# MINI_SAM_2017-01-015.net
KiCad netlist of a schematic drawn in EAGLE
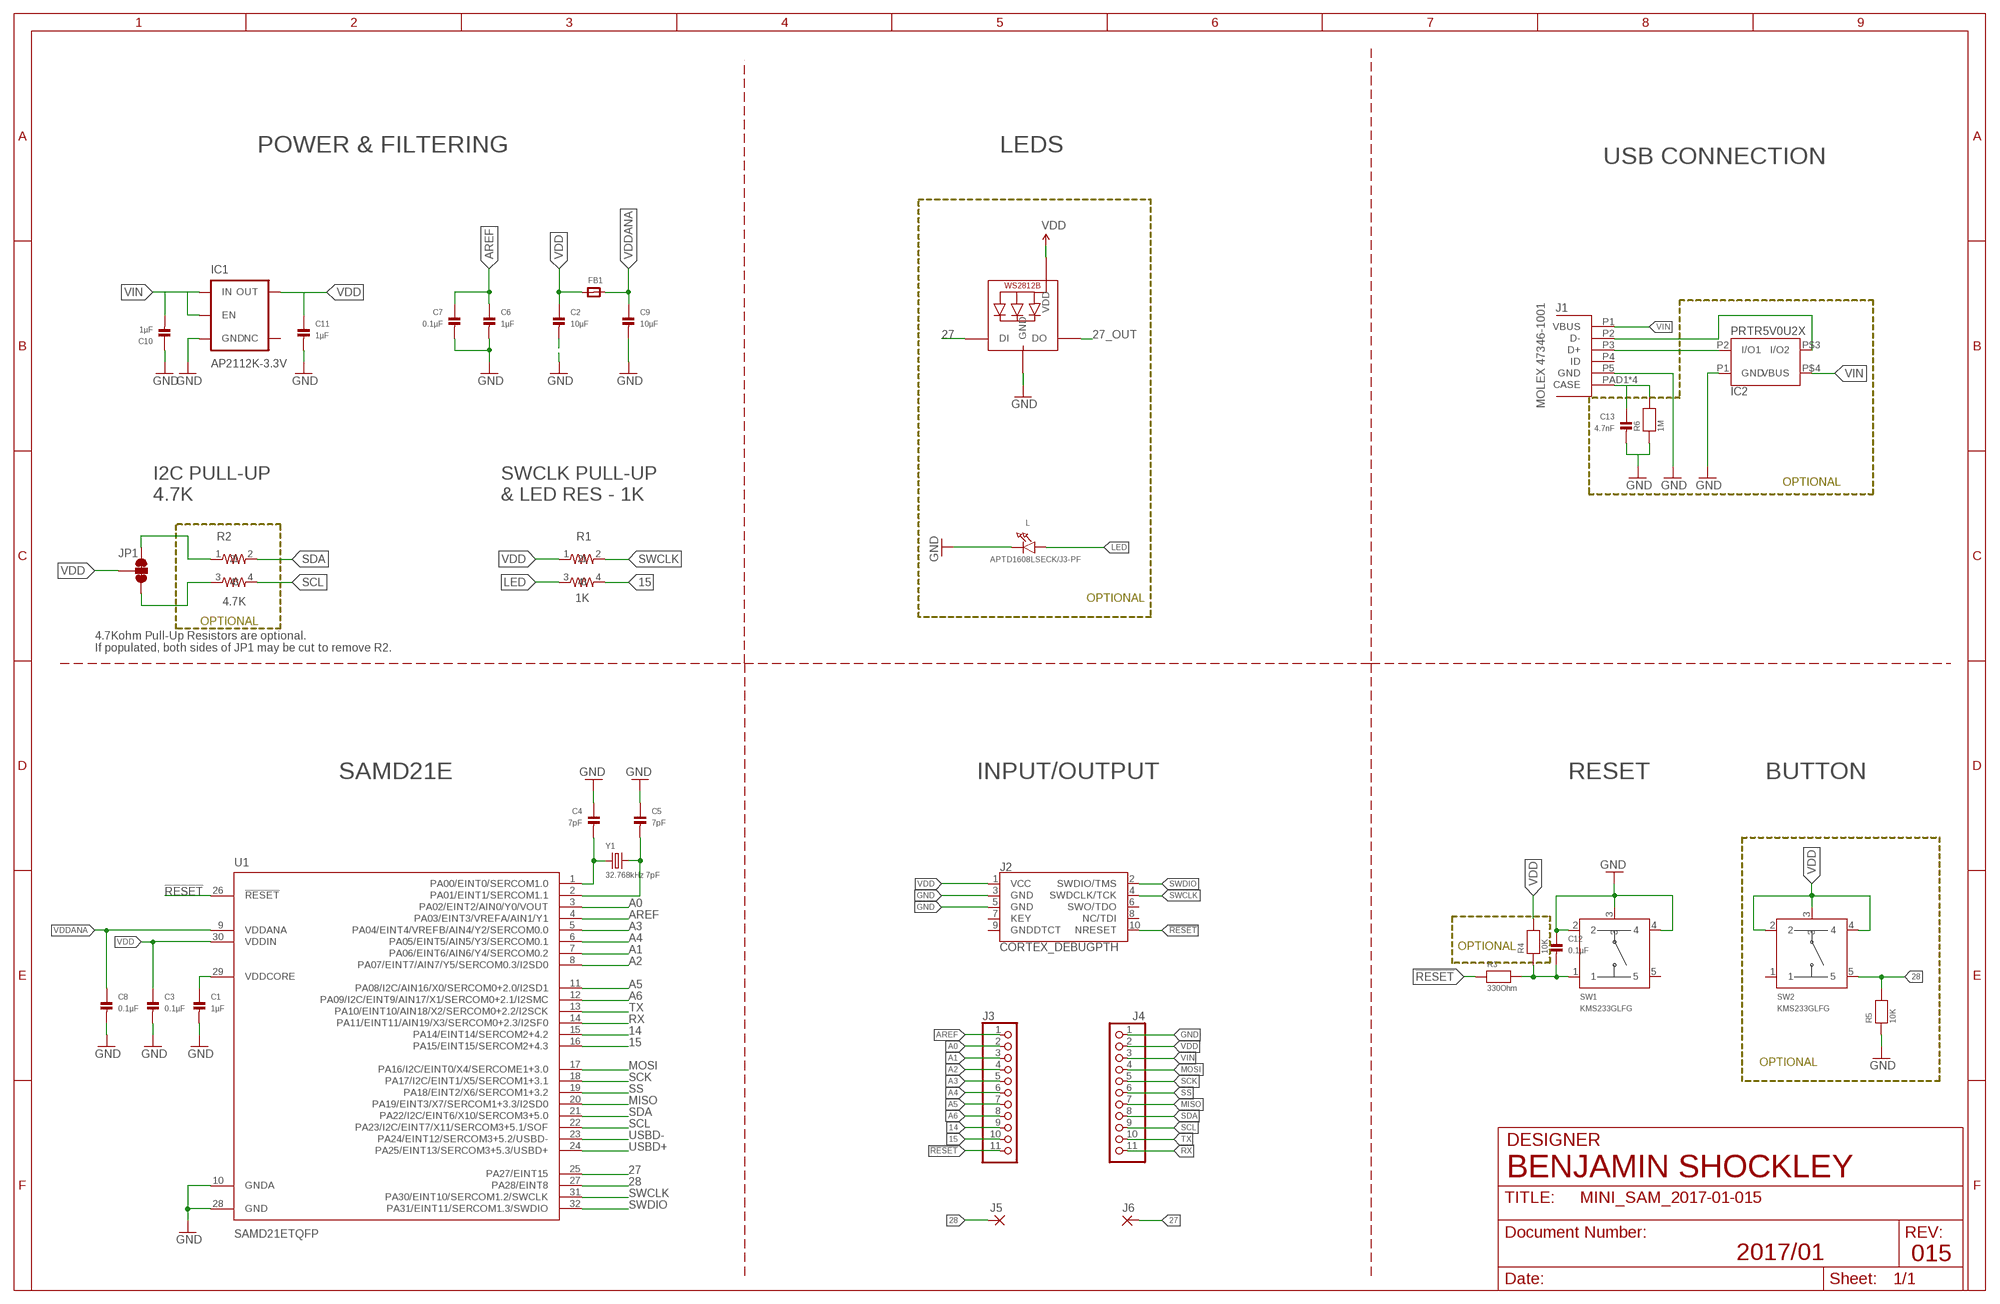
[diagram p0: schematic, sheet 1]

(export (version "E")
  (design (tool "Eeschema 10.0.6"))
  (components
    (comp (ref "C1")
      (value "1µF")
      (footprint "eagle-import:_0805MP")
      (libsource (lib "eagle-import") (part "CAP_CERAMIC_0805MP"))
    )
    (comp (ref "C2")
      (value "10µF")
      (footprint "eagle-import:_0805MP")
      (libsource (lib "eagle-import") (part "CAP_CERAMIC_0805MP"))
    )
    (comp (ref "C3")
      (value "0.1µF")
      (footprint "eagle-import:_0805MP")
      (libsource (lib "eagle-import") (part "CAP_CERAMIC_0805MP"))
    )
    (comp (ref "C4")
      (value "7pF")
      (footprint "eagle-import:_0805MP")
      (libsource (lib "eagle-import") (part "CAP_CERAMIC_0805MP"))
    )
    (comp (ref "C5")
      (value "7pF")
      (footprint "eagle-import:_0805MP")
      (libsource (lib "eagle-import") (part "CAP_CERAMIC_0805MP"))
    )
    (comp (ref "C6")
      (value "1µF")
      (footprint "eagle-import:_0805MP")
      (libsource (lib "eagle-import") (part "CAP_CERAMIC_0805MP"))
    )
    (comp (ref "C7")
      (value "0.1µF")
      (footprint "eagle-import:_0805MP")
      (libsource (lib "eagle-import") (part "CAP_CERAMIC_0805MP"))
    )
    (comp (ref "C8")
      (value "0.1µF")
      (footprint "eagle-import:_0805MP")
      (libsource (lib "eagle-import") (part "CAP_CERAMIC_0805MP"))
    )
    (comp (ref "C9")
      (value "10µF")
      (footprint "eagle-import:_0805MP")
      (libsource (lib "eagle-import") (part "CAP_CERAMIC_0805MP"))
    )
    (comp (ref "C10")
      (value "1µF")
      (footprint "eagle-import:_0805MP")
      (libsource (lib "eagle-import") (part "CAP_CERAMIC_0805MP"))
    )
    (comp (ref "C11")
      (value "1µF")
      (footprint "eagle-import:_0805MP")
      (libsource (lib "eagle-import") (part "CAP_CERAMIC_0805MP"))
    )
    (comp (ref "C12")
      (value "0.1µF")
      (footprint "eagle-import:_0805MP")
      (libsource (lib "eagle-import") (part "CAP_CERAMIC_0805MP"))
    )
    (comp (ref "C13")
      (value "4.7nF")
      (footprint "eagle-import:_0805MP")
      (libsource (lib "eagle-import") (part "CAP_CERAMIC_0805MP"))
    )
    (comp (ref "FB1")
      (value "FERRITE_0805MP")
      (footprint "eagle-import:_0805MP")
      (libsource (lib "eagle-import") (part "FERRITE_0805MP"))
    )
    (comp (ref "IC1")
      (value "AP2112K-3.3V")
      (footprint "eagle-import:SOT23-5")
      (libsource (lib "eagle-import") (part "V_REG_AP2112K-3.3V"))
    )
    (comp (ref "IC2")
      (value "PRTR5V0U2X")
      (footprint "eagle-import:SOT143B_REFLOW")
      (libsource (lib "eagle-import") (part "PRTR5V0U2X"))
    )
    (comp (ref "J1")
      (value "MOLEX_47346-100147346")
      (footprint "eagle-import:MOLEX_47346-1001")
      (libsource (lib "eagle-import") (part "MOLEX_47346-100147346"))
    )
    (comp (ref "J2")
      (value "CORTEX_DEBUGPTH")
      (footprint "eagle-import:2X5-PTH-1.27MM")
      (libsource (lib "eagle-import") (part "CORTEX_DEBUGPTH"))
    )
    (comp (ref "J3")
      (value "PINHD-1X111X11_SMT")
      (footprint "eagle-import:1X11_SMT")
      (libsource (lib "eagle-import") (part "PINHD-1X111X11_SMT"))
    )
    (comp (ref "J4")
      (value "PINHD-1X111X11_SMT")
      (footprint "eagle-import:1X11_SMT")
      (libsource (lib "eagle-import") (part "PINHD-1X111X11_SMT"))
    )
    (comp (ref "J5")
      (value "FR11_PAD2MMX1MM")
      (footprint "eagle-import:SMD2MMX1MM")
      (libsource (lib "eagle-import") (part "FR11_PAD2MMX1MM"))
    )
    (comp (ref "J6")
      (value "FR11_PAD2MMX1MM")
      (footprint "eagle-import:SMD2MMX1MM")
      (libsource (lib "eagle-import") (part "FR11_PAD2MMX1MM"))
    )
    (comp (ref "JP1")
      (value "JUMPER-SMT_3_2-NC_TRACE_NO-SILK")
      (footprint "eagle-import:SMT-JUMPER_3_2-NC_TRACE_NO-SILK")
      (libsource (lib "eagle-import") (part "JUMPER-SMT_3_2-NC_TRACE_NO-SILK"))
    )
    (comp (ref "L")
      (value "APTD1608LSECK/J3-PF")
      (footprint "eagle-import:CHIPLED_0603_NOOUTLINE")
      (libsource (lib "eagle-import") (part "LED0603_NOOUTLINE"))
    )
    (comp (ref "R1")
      (value "1K")
      (footprint "eagle-import:RESISTOR_ARRAY_0606")
      (libsource (lib "eagle-import") (part "RESISTOR_ARRAY_2"))
    )
    (comp (ref "R2")
      (value "4.7K")
      (footprint "eagle-import:RESISTOR_ARRAY_0606")
      (libsource (lib "eagle-import") (part "RESISTOR_ARRAY_2"))
    )
    (comp (ref "R3")
      (value "330Ohm")
      (footprint "eagle-import:_0805MP")
      (libsource (lib "eagle-import") (part "RESISTOR_0805MP"))
    )
    (comp (ref "R4")
      (value "10K")
      (footprint "eagle-import:_0805MP")
      (libsource (lib "eagle-import") (part "RESISTOR_0805MP"))
    )
    (comp (ref "R5")
      (value "10K")
      (footprint "eagle-import:_0805MP")
      (libsource (lib "eagle-import") (part "RESISTOR_0805MP"))
    )
    (comp (ref "R6")
      (value "1M")
      (footprint "eagle-import:_0805MP")
      (libsource (lib "eagle-import") (part "RESISTOR_0805MP"))
    )
    (comp (ref "STATUS")
      (value "WS2812B3535")
      (footprint "eagle-import:LED3535")
      (libsource (lib "eagle-import") (part "WS2812B3535"))
    )
    (comp (ref "SW1")
      (value "KMS233GLFG")
      (footprint "eagle-import:KMS_SWITCH")
      (libsource (lib "eagle-import") (part "KMS_SWITCHKMS"))
    )
    (comp (ref "SW2")
      (value "KMS233GLFG")
      (footprint "eagle-import:KMS_SWITCH")
      (libsource (lib "eagle-import") (part "KMS_SWITCHKMS"))
    )
    (comp (ref "U1")
      (value "SAMD21ETQFP")
      (footprint "eagle-import:TQFP32-08")
      (libsource (lib "eagle-import") (part "SAMD21ETQFP"))
    )
    (comp (ref "Y1")
      (value "32.768kHz 7pF")
      (footprint "eagle-import:_0805MP")
      (libsource (lib "eagle-import") (part "CRYSTAL0805PACKAGE"))
    )
  )
  (nets
    (net (code "1") (name "/27_OUT") (class "Default")
      (node (ref "STATUS") (pin "3") (pinfunction "DO_3") (pintype "output"))
    )
    (net (code "2") (name "/USBD+") (class "Default")
      (node (ref "IC2") (pin "P2") (pinfunction "I/O1_P2") (pintype "bidirectional"))
      (node (ref "J1") (pin "P3") (pinfunction "D+_P3") (pintype "bidirectional"))
      (node (ref "U1") (pin "24") (pinfunction "PA25/EINT13/SERCOM3+5.3/USBD+_24") (pintype "bidirectional"))
    )
    (net (code "3") (name "/USBD-") (class "Default")
      (node (ref "IC2") (pin "P$3") (pinfunction "I/O2_P$3") (pintype "bidirectional"))
      (node (ref "J1") (pin "P2") (pinfunction "D-_P2") (pintype "bidirectional"))
      (node (ref "U1") (pin "23") (pinfunction "PA24/EINT12/SERCOM3+5.2/USBD-_23") (pintype "bidirectional"))
    )
    (net (code "4") (name "/~{RESET}") (class "Default")
      (node (ref "J2") (pin "10") (pinfunction "NRESET_10") (pintype "bidirectional"))
      (node (ref "J3") (pin "11") (pinfunction "11_11") (pintype "passive"))
      (node (ref "R3") (pin "1") (pinfunction "1_1") (pintype "passive"))
      (node (ref "U1") (pin "26") (pinfunction "~{RESET}_26") (pintype "bidirectional"))
    )
    (net (code "5") (name "14") (class "Default")
      (node (ref "J3") (pin "9") (pinfunction "9_9") (pintype "passive"))
      (node (ref "U1") (pin "15") (pinfunction "PA14/EINT14/SERCOM2+4.2_15") (pintype "bidirectional"))
    )
    (net (code "6") (name "15") (class "Default")
      (node (ref "J3") (pin "10") (pinfunction "10_10") (pintype "passive"))
      (node (ref "R1") (pin "4") (pinfunction "4_4") (pintype "passive"))
      (node (ref "U1") (pin "16") (pinfunction "PA15/EINT15/SERCOM2+4.3_16") (pintype "bidirectional"))
    )
    (net (code "7") (name "27") (class "Default")
      (node (ref "J6") (pin "P$1") (pinfunction "P_P$1") (pintype "passive"))
      (node (ref "STATUS") (pin "1") (pinfunction "DI_1") (pintype "input"))
      (node (ref "U1") (pin "25") (pinfunction "PA27/EINT15_25") (pintype "bidirectional"))
    )
    (net (code "8") (name "28") (class "Default")
      (node (ref "J5") (pin "P$1") (pinfunction "P_P$1") (pintype "passive"))
      (node (ref "R5") (pin "2") (pinfunction "2_2") (pintype "passive"))
      (node (ref "SW2") (pin "5") (pinfunction "5_5") (pintype "bidirectional"))
      (node (ref "U1") (pin "27") (pinfunction "PA28/EINT8_27") (pintype "bidirectional"))
    )
    (net (code "9") (name "A0") (class "Default")
      (node (ref "J3") (pin "2") (pinfunction "2_2") (pintype "passive"))
      (node (ref "U1") (pin "3") (pinfunction "PA02/EINT2/AIN0/Y0/VOUT_3") (pintype "bidirectional"))
    )
    (net (code "10") (name "A1") (class "Default")
      (node (ref "J3") (pin "3") (pinfunction "3_3") (pintype "passive"))
      (node (ref "U1") (pin "7") (pinfunction "PA06/EINT6/AIN6/Y4/SERCOM0.2_7") (pintype "bidirectional"))
    )
    (net (code "11") (name "A2") (class "Default")
      (node (ref "J3") (pin "4") (pinfunction "4_4") (pintype "passive"))
      (node (ref "U1") (pin "8") (pinfunction "PA07/EINT7/AIN7/Y5/SERCOM0.3/I2SD0_8") (pintype "bidirectional"))
    )
    (net (code "12") (name "A3") (class "Default")
      (node (ref "J3") (pin "5") (pinfunction "5_5") (pintype "passive"))
      (node (ref "U1") (pin "5") (pinfunction "PA04/EINT4/VREFB/AIN4/Y2/SERCOM0.0_5") (pintype "bidirectional"))
    )
    (net (code "13") (name "A4") (class "Default")
      (node (ref "J3") (pin "6") (pinfunction "6_6") (pintype "passive"))
      (node (ref "U1") (pin "6") (pinfunction "PA05/EINT5/AIN5/Y3/SERCOM0.1_6") (pintype "bidirectional"))
    )
    (net (code "14") (name "A5") (class "Default")
      (node (ref "J3") (pin "7") (pinfunction "7_7") (pintype "passive"))
      (node (ref "U1") (pin "11") (pinfunction "PA08/I2C/AIN16/X0/SERCOM0+2.0/I2SD1_11") (pintype "bidirectional"))
    )
    (net (code "15") (name "A6") (class "Default")
      (node (ref "J3") (pin "8") (pinfunction "8_8") (pintype "passive"))
      (node (ref "U1") (pin "12") (pinfunction "PA09/I2C/EINT9/AIN17/X1/SERCOM0+2.1/I2SMC_12") (pintype "bidirectional"))
    )
    (net (code "16") (name "AREF") (class "Default")
      (node (ref "C6") (pin "1") (pinfunction "P$1_1") (pintype "passive"))
      (node (ref "C7") (pin "1") (pinfunction "P$1_1") (pintype "passive"))
      (node (ref "J3") (pin "1") (pinfunction "1_1") (pintype "passive"))
      (node (ref "U1") (pin "4") (pinfunction "PA03/EINT3/VREFA/AIN1/Y1_4") (pintype "bidirectional"))
    )
    (net (code "17") (name "GND") (class "Default")
      (node (ref "C1") (pin "2") (pinfunction "P$2_2") (pintype "passive"))
      (node (ref "C10") (pin "1") (pinfunction "P$1_1") (pintype "passive"))
      (node (ref "C11") (pin "2") (pinfunction "P$2_2") (pintype "passive"))
      (node (ref "C12") (pin "1") (pinfunction "P$1_1") (pintype "passive"))
      (node (ref "C13") (pin "2") (pinfunction "P$2_2") (pintype "passive"))
      (node (ref "C2") (pin "2") (pinfunction "P$2_2") (pintype "passive"))
      (node (ref "C3") (pin "2") (pinfunction "P$2_2") (pintype "passive"))
      (node (ref "C4") (pin "1") (pinfunction "P$1_1") (pintype "passive"))
      (node (ref "C5") (pin "1") (pinfunction "P$1_1") (pintype "passive"))
      (node (ref "C6") (pin "2") (pinfunction "P$2_2") (pintype "passive"))
      (node (ref "C7") (pin "2") (pinfunction "P$2_2") (pintype "passive"))
      (node (ref "C8") (pin "2") (pinfunction "P$2_2") (pintype "passive"))
      (node (ref "C9") (pin "2") (pinfunction "P$2_2") (pintype "passive"))
      (node (ref "IC1") (pin "2") (pinfunction "GND_2") (pintype "input"))
      (node (ref "IC2") (pin "P1") (pinfunction "GND_P1") (pintype "bidirectional"))
      (node (ref "J1") (pin "P5") (pinfunction "GND_P5") (pintype "power_in"))
      (node (ref "J2") (pin "3") (pinfunction "GND_3") (pintype "bidirectional"))
      (node (ref "J2") (pin "5") (pinfunction "GND_5") (pintype "bidirectional"))
      (node (ref "J4") (pin "1") (pinfunction "1_1") (pintype "passive"))
      (node (ref "L") (pin "C") (pinfunction "C_C") (pintype "passive"))
      (node (ref "R5") (pin "1") (pinfunction "1_1") (pintype "passive"))
      (node (ref "R6") (pin "1") (pinfunction "1_1") (pintype "passive"))
      (node (ref "STATUS") (pin "4") (pinfunction "GND_4") (pintype "power_in"))
      (node (ref "SW1") (pin "2") (pinfunction "2_2") (pintype "bidirectional"))
      (node (ref "SW1") (pin "3") (pinfunction "3_3") (pintype "bidirectional"))
      (node (ref "SW1") (pin "4") (pinfunction "4_4") (pintype "bidirectional"))
      (node (ref "U1") (pin "10") (pinfunction "GNDA_10") (pintype "power_in"))
      (node (ref "U1") (pin "28") (pinfunction "GND_28") (pintype "power_in"))
    )
    (net (code "18") (name "LED") (class "Default")
      (node (ref "L") (pin "A") (pinfunction "A_A") (pintype "passive"))
      (node (ref "R1") (pin "3") (pinfunction "3_3") (pintype "passive"))
    )
    (net (code "19") (name "MISO") (class "Default")
      (node (ref "J4") (pin "7") (pinfunction "7_7") (pintype "passive"))
      (node (ref "U1") (pin "20") (pinfunction "PA19/EINT3/X7/SERCOM1+3.3/I2SD0_20") (pintype "bidirectional"))
    )
    (net (code "20") (name "MOSI") (class "Default")
      (node (ref "J4") (pin "4") (pinfunction "4_4") (pintype "passive"))
      (node (ref "U1") (pin "17") (pinfunction "PA16/I2C/EINT0/X4/SERCOME1+3.0_17") (pintype "bidirectional"))
    )
    (net (code "21") (name "Net-(C1-P$1)") (class "Default")
      (node (ref "C1") (pin "1") (pinfunction "P$1_1") (pintype "passive"))
      (node (ref "U1") (pin "29") (pinfunction "VDDCORE_29") (pintype "power_in"))
    )
    (net (code "22") (name "Net-(C4-P$2)") (class "Default")
      (node (ref "C4") (pin "2") (pinfunction "P$2_2") (pintype "passive"))
      (node (ref "U1") (pin "1") (pinfunction "PA00/EINT0/SERCOM1.0_1") (pintype "bidirectional"))
      (node (ref "Y1") (pin "1") (pinfunction "1_1") (pintype "passive"))
    )
    (net (code "23") (name "Net-(C5-P$2)") (class "Default")
      (node (ref "C5") (pin "2") (pinfunction "P$2_2") (pintype "passive"))
      (node (ref "U1") (pin "2") (pinfunction "PA01/EINT1/SERCOM1.1_2") (pintype "bidirectional"))
      (node (ref "Y1") (pin "2") (pinfunction "2_2") (pintype "passive"))
    )
    (net (code "24") (name "Net-(C12-P$2)") (class "Default")
      (node (ref "C12") (pin "2") (pinfunction "P$2_2") (pintype "passive"))
      (node (ref "R3") (pin "2") (pinfunction "2_2") (pintype "passive"))
      (node (ref "R4") (pin "1") (pinfunction "1_1") (pintype "passive"))
      (node (ref "SW1") (pin "1") (pinfunction "1_1") (pintype "bidirectional"))
    )
    (net (code "25") (name "Net-(C13-P$1)") (class "Default")
      (node (ref "C13") (pin "1") (pinfunction "P$1_1") (pintype "passive"))
      (node (ref "J1") (pin "PAD1") (pinfunction "CASE_PAD1") (pintype "bidirectional"))
      (node (ref "J1") (pin "PAD2") (pinfunction "CASE_PAD2") (pintype "bidirectional"))
      (node (ref "J1") (pin "PAD3") (pinfunction "CASE_PAD3") (pintype "bidirectional"))
      (node (ref "J1") (pin "PAD4") (pinfunction "CASE_PAD4") (pintype "bidirectional"))
      (node (ref "R6") (pin "2") (pinfunction "2_2") (pintype "passive"))
    )
    (net (code "26") (name "Net-(JP1-Pad1)") (class "Default")
      (node (ref "JP1") (pin "1") (pinfunction "1_1") (pintype "passive"))
      (node (ref "R2") (pin "1") (pinfunction "1_1") (pintype "passive"))
    )
    (net (code "27") (name "Net-(JP1-Pad3)") (class "Default")
      (node (ref "JP1") (pin "3") (pinfunction "3_3") (pintype "passive"))
      (node (ref "R2") (pin "3") (pinfunction "3_3") (pintype "passive"))
    )
    (net (code "28") (name "RX") (class "Default")
      (node (ref "J4") (pin "11") (pinfunction "11_11") (pintype "passive"))
      (node (ref "U1") (pin "14") (pinfunction "PA11/EINT11/AIN19/X3/SERCOM0+2.3/I2SF0_14") (pintype "bidirectional"))
    )
    (net (code "29") (name "SCK") (class "Default")
      (node (ref "J4") (pin "5") (pinfunction "5_5") (pintype "passive"))
      (node (ref "U1") (pin "18") (pinfunction "PA17/I2C/EINT1/X5/SERCOM1+3.1_18") (pintype "bidirectional"))
    )
    (net (code "30") (name "SCL") (class "Default")
      (node (ref "J4") (pin "9") (pinfunction "9_9") (pintype "passive"))
      (node (ref "R2") (pin "4") (pinfunction "4_4") (pintype "passive"))
      (node (ref "U1") (pin "22") (pinfunction "PA23/I2C/EINT7/X11/SERCOM3+5.1/SOF_22") (pintype "bidirectional"))
    )
    (net (code "31") (name "SDA") (class "Default")
      (node (ref "J4") (pin "8") (pinfunction "8_8") (pintype "passive"))
      (node (ref "R2") (pin "2") (pinfunction "2_2") (pintype "passive"))
      (node (ref "U1") (pin "21") (pinfunction "PA22/I2C/EINT6/X10/SERCOM3+5.0_21") (pintype "bidirectional"))
    )
    (net (code "32") (name "SS") (class "Default")
      (node (ref "J4") (pin "6") (pinfunction "6_6") (pintype "passive"))
      (node (ref "U1") (pin "19") (pinfunction "PA18/EINT2/X6/SERCOM1+3.2_19") (pintype "bidirectional"))
    )
    (net (code "33") (name "SWCLK") (class "Default")
      (node (ref "J2") (pin "4") (pinfunction "SWDCLK/TCK_4") (pintype "bidirectional"))
      (node (ref "R1") (pin "2") (pinfunction "2_2") (pintype "passive"))
      (node (ref "U1") (pin "31") (pinfunction "PA30/EINT10/SERCOM1.2/SWCLK_31") (pintype "bidirectional"))
    )
    (net (code "34") (name "SWDIO") (class "Default")
      (node (ref "J2") (pin "2") (pinfunction "SWDIO/TMS_2") (pintype "bidirectional"))
      (node (ref "U1") (pin "32") (pinfunction "PA31/EINT11/SERCOM1.3/SWDIO_32") (pintype "bidirectional"))
    )
    (net (code "35") (name "TX") (class "Default")
      (node (ref "J4") (pin "10") (pinfunction "10_10") (pintype "passive"))
      (node (ref "U1") (pin "13") (pinfunction "PA10/EINT10/AIN18/X2/SERCOM0+2.2/I2SCK_13") (pintype "bidirectional"))
    )
    (net (code "36") (name "VDD") (class "Default")
      (node (ref "C11") (pin "1") (pinfunction "P$1_1") (pintype "passive"))
      (node (ref "C2") (pin "1") (pinfunction "P$1_1") (pintype "passive"))
      (node (ref "C3") (pin "1") (pinfunction "P$1_1") (pintype "passive"))
      (node (ref "FB1") (pin "1") (pinfunction "P$1_1") (pintype "passive"))
      (node (ref "IC1") (pin "5") (pinfunction "OUT_5") (pintype "passive"))
      (node (ref "J2") (pin "1") (pinfunction "VCC_1") (pintype "bidirectional"))
      (node (ref "J4") (pin "2") (pinfunction "2_2") (pintype "passive"))
      (node (ref "JP1") (pin "2") (pinfunction "2_2") (pintype "passive"))
      (node (ref "R1") (pin "1") (pinfunction "1_1") (pintype "passive"))
      (node (ref "R4") (pin "2") (pinfunction "2_2") (pintype "passive"))
      (node (ref "STATUS") (pin "2") (pinfunction "VDD_2") (pintype "power_in"))
      (node (ref "SW2") (pin "2") (pinfunction "2_2") (pintype "bidirectional"))
      (node (ref "SW2") (pin "3") (pinfunction "3_3") (pintype "bidirectional"))
      (node (ref "SW2") (pin "4") (pinfunction "4_4") (pintype "bidirectional"))
      (node (ref "U1") (pin "30") (pinfunction "VDDIN_30") (pintype "power_in"))
    )
    (net (code "37") (name "VDDANA") (class "Default")
      (node (ref "C8") (pin "1") (pinfunction "P$1_1") (pintype "passive"))
      (node (ref "C9") (pin "1") (pinfunction "P$1_1") (pintype "passive"))
      (node (ref "FB1") (pin "2") (pinfunction "P$2_2") (pintype "passive"))
      (node (ref "U1") (pin "9") (pinfunction "VDDANA_9") (pintype "power_in"))
    )
    (net (code "38") (name "VIN") (class "Default")
      (node (ref "C10") (pin "2") (pinfunction "P$2_2") (pintype "passive"))
      (node (ref "IC1") (pin "1") (pinfunction "IN_1") (pintype "input"))
      (node (ref "IC1") (pin "3") (pinfunction "EN_3") (pintype "input"))
      (node (ref "IC2") (pin "P$4") (pinfunction "VBUS_P$4") (pintype "bidirectional"))
      (node (ref "J1") (pin "P1") (pinfunction "VBUS_P1") (pintype "power_in"))
      (node (ref "J4") (pin "3") (pinfunction "3_3") (pintype "passive"))
    )
    (net (code "39") (name "unconnected-(IC1-NC-Pad4)") (class "Default")
      (node (ref "IC1") (pin "4") (pinfunction "NC_4") (pintype "input"))
    )
    (net (code "40") (name "unconnected-(J1-ID-PadP4)") (class "Default")
      (node (ref "J1") (pin "P4") (pinfunction "ID_P4") (pintype "bidirectional"))
    )
    (net (code "41") (name "unconnected-(J2-GNDDTCT-Pad9)") (class "Default")
      (node (ref "J2") (pin "9") (pinfunction "GNDDTCT_9") (pintype "bidirectional"))
    )
    (net (code "42") (name "unconnected-(J2-KEY-Pad7)") (class "Default")
      (node (ref "J2") (pin "7") (pinfunction "KEY_7") (pintype "bidirectional"))
    )
    (net (code "43") (name "unconnected-(J2-NC{slash}TDI-Pad8)") (class "Default")
      (node (ref "J2") (pin "8") (pinfunction "NC/TDI_8") (pintype "bidirectional"))
    )
    (net (code "44") (name "unconnected-(J2-SWO{slash}TDO-Pad6)") (class "Default")
      (node (ref "J2") (pin "6") (pinfunction "SWO/TDO_6") (pintype "bidirectional"))
    )
    (net (code "45") (name "unconnected-(SW1-Pad5)") (class "Default")
      (node (ref "SW1") (pin "5") (pinfunction "5_5") (pintype "bidirectional"))
    )
    (net (code "46") (name "unconnected-(SW2-Pad1)") (class "Default")
      (node (ref "SW2") (pin "1") (pinfunction "1_1") (pintype "bidirectional"))
    )
  )
)
